# Sheet2.net
KiCad netlist of a schematic drawn in Altium Designer
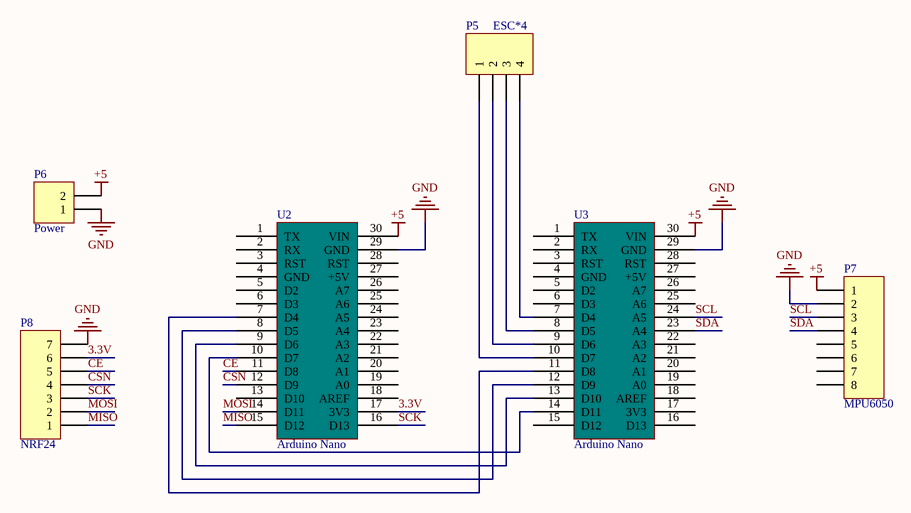
[diagram p0: Sheet2.SchDoc]

(export (version "E")
  (design (tool "Eeschema 10.0.6"))
  (components
    (comp (ref "P5")
      (value "ESC*4")
      (footprint "HDR1X4")
      (description "Header, 4-Pin")
      (fields (field (name "PUBLISHER") "Altium Limited"))
      (libsource (lib "Miscellaneous Connectors") (part "Header 4"))
    )
    (comp (ref "P6")
      (value "Power")
      (footprint "HDR1X2")
      (description "Header, 2-Pin")
      (fields (field (name "PUBLISHER") "Altium Limited"))
      (libsource (lib "Miscellaneous Connectors") (part "Header 2"))
    )
    (comp (ref "P7")
      (value "MPU6050")
      (footprint "HDR1X8")
      (description "Header, 8-Pin")
      (fields (field (name "PUBLISHER") "Altium Limited"))
      (libsource (lib "Miscellaneous Connectors") (part "Header 8"))
    )
    (comp (ref "P8")
      (value "NRF24")
      (footprint "HDR1X7")
      (description "Header, 7-Pin")
      (fields (field (name "PUBLISHER") "Altium Limited"))
      (libsource (lib "Miscellaneous Connectors") (part "Header 7"))
    )
    (comp (ref "U2")
      (value "Arduino Nano")
      (footprint "PCBComponent_1")
      (libsource (lib "Nano") (part "Component_1"))
    )
    (comp (ref "U3")
      (value "Arduino Nano")
      (footprint "PCBComponent_1")
      (libsource (lib "Nano") (part "Component_1"))
    )
  )
  (nets
    (net (code "1") (name "+5") (class "Default")
      (node (ref "P6") (pin "2") (pinfunction "2_2") (pintype "passive"))
      (node (ref "P7") (pin "1") (pinfunction "1_1") (pintype "passive"))
      (node (ref "U2") (pin "30") (pinfunction "VIN_30") (pintype "passive"))
      (node (ref "U3") (pin "30") (pinfunction "VIN_30") (pintype "passive"))
    )
    (net (code "2") (name "/3.3V") (class "Default")
      (node (ref "P8") (pin "6") (pinfunction "6_6") (pintype "passive"))
      (node (ref "U2") (pin "17") (pinfunction "3V3_17") (pintype "passive"))
    )
    (net (code "3") (name "/CE") (class "Default")
      (node (ref "P8") (pin "5") (pinfunction "5_5") (pintype "passive"))
      (node (ref "U2") (pin "11") (pinfunction "D8_11") (pintype "passive"))
    )
    (net (code "4") (name "/CSN") (class "Default")
      (node (ref "P8") (pin "4") (pinfunction "4_4") (pintype "passive"))
      (node (ref "U2") (pin "12") (pinfunction "D9_12") (pintype "passive"))
    )
    (net (code "5") (name "/MISO") (class "Default")
      (node (ref "P8") (pin "1") (pinfunction "1_1") (pintype "passive"))
      (node (ref "U2") (pin "15") (pinfunction "D12_15") (pintype "passive"))
    )
    (net (code "6") (name "/MOSI") (class "Default")
      (node (ref "P8") (pin "2") (pinfunction "2_2") (pintype "passive"))
      (node (ref "U2") (pin "14") (pinfunction "D11_14") (pintype "passive"))
    )
    (net (code "7") (name "/SCK") (class "Default")
      (node (ref "P8") (pin "3") (pinfunction "3_3") (pintype "passive"))
      (node (ref "U2") (pin "16") (pinfunction "D13_16") (pintype "passive"))
    )
    (net (code "8") (name "/SCL") (class "Default")
      (node (ref "P7") (pin "3") (pinfunction "3_3") (pintype "passive"))
      (node (ref "U3") (pin "24") (pinfunction "A5_24") (pintype "passive"))
    )
    (net (code "9") (name "/SDA") (class "Default")
      (node (ref "P7") (pin "4") (pinfunction "4_4") (pintype "passive"))
      (node (ref "U3") (pin "23") (pinfunction "A4_23") (pintype "passive"))
    )
    (net (code "10") (name "GND") (class "Default")
      (node (ref "P6") (pin "1") (pinfunction "1_1") (pintype "passive"))
      (node (ref "P7") (pin "2") (pinfunction "2_2") (pintype "passive"))
      (node (ref "P8") (pin "7") (pinfunction "7_7") (pintype "passive"))
      (node (ref "U2") (pin "29") (pinfunction "GND_29") (pintype "passive"))
      (node (ref "U3") (pin "29") (pinfunction "GND_29") (pintype "passive"))
    )
    (net (code "11") (name "Net-(U2-D4)") (class "Default")
      (node (ref "U2") (pin "7") (pinfunction "D4_7") (pintype "passive"))
      (node (ref "U3") (pin "11") (pinfunction "D8_11") (pintype "passive"))
    )
    (net (code "12") (name "Net-(U2-D5)") (class "Default")
      (node (ref "U2") (pin "8") (pinfunction "D5_8") (pintype "passive"))
      (node (ref "U3") (pin "12") (pinfunction "D9_12") (pintype "passive"))
    )
    (net (code "13") (name "Net-(U2-D6)") (class "Default")
      (node (ref "U2") (pin "9") (pinfunction "D6_9") (pintype "passive"))
      (node (ref "U3") (pin "13") (pinfunction "D10_13") (pintype "passive"))
    )
    (net (code "14") (name "Net-(U2-D7)") (class "Default")
      (node (ref "U2") (pin "10") (pinfunction "D7_10") (pintype "passive"))
      (node (ref "U3") (pin "14") (pinfunction "D11_14") (pintype "passive"))
    )
    (net (code "15") (name "Net-(U3-D4)") (class "Default")
      (node (ref "P5") (pin "4") (pinfunction "4_4") (pintype "passive"))
      (node (ref "U3") (pin "7") (pinfunction "D4_7") (pintype "passive"))
    )
    (net (code "16") (name "Net-(U3-D5)") (class "Default")
      (node (ref "P5") (pin "3") (pinfunction "3_3") (pintype "passive"))
      (node (ref "U3") (pin "8") (pinfunction "D5_8") (pintype "passive"))
    )
    (net (code "17") (name "Net-(U3-D6)") (class "Default")
      (node (ref "P5") (pin "2") (pinfunction "2_2") (pintype "passive"))
      (node (ref "U3") (pin "9") (pinfunction "D6_9") (pintype "passive"))
    )
    (net (code "18") (name "Net-(U3-D7)") (class "Default")
      (node (ref "P5") (pin "1") (pinfunction "1_1") (pintype "passive"))
      (node (ref "U3") (pin "10") (pinfunction "D7_10") (pintype "passive"))
    )
    (net (code "19") (name "unconnected-(P7-Pad5)") (class "Default")
      (node (ref "P7") (pin "5") (pinfunction "5_5") (pintype "passive"))
    )
    (net (code "20") (name "unconnected-(P7-Pad6)") (class "Default")
      (node (ref "P7") (pin "6") (pinfunction "6_6") (pintype "passive"))
    )
    (net (code "21") (name "unconnected-(P7-Pad7)") (class "Default")
      (node (ref "P7") (pin "7") (pinfunction "7_7") (pintype "passive"))
    )
    (net (code "22") (name "unconnected-(P7-Pad8)") (class "Default")
      (node (ref "P7") (pin "8") (pinfunction "8_8") (pintype "passive"))
    )
    (net (code "23") (name "unconnected-(U2-+5V-Pad27)") (class "Default")
      (node (ref "U2") (pin "27") (pinfunction "+5V_27") (pintype "passive"))
    )
    (net (code "24") (name "unconnected-(U2-A0-Pad19)") (class "Default")
      (node (ref "U2") (pin "19") (pinfunction "A0_19") (pintype "passive"))
    )
    (net (code "25") (name "unconnected-(U2-A1-Pad20)") (class "Default")
      (node (ref "U2") (pin "20") (pinfunction "A1_20") (pintype "passive"))
    )
    (net (code "26") (name "unconnected-(U2-A2-Pad21)") (class "Default")
      (node (ref "U2") (pin "21") (pinfunction "A2_21") (pintype "passive"))
    )
    (net (code "27") (name "unconnected-(U2-A3-Pad22)") (class "Default")
      (node (ref "U2") (pin "22") (pinfunction "A3_22") (pintype "passive"))
    )
    (net (code "28") (name "unconnected-(U2-A4-Pad23)") (class "Default")
      (node (ref "U2") (pin "23") (pinfunction "A4_23") (pintype "passive"))
    )
    (net (code "29") (name "unconnected-(U2-A5-Pad24)") (class "Default")
      (node (ref "U2") (pin "24") (pinfunction "A5_24") (pintype "passive"))
    )
    (net (code "30") (name "unconnected-(U2-A6-Pad25)") (class "Default")
      (node (ref "U2") (pin "25") (pinfunction "A6_25") (pintype "passive"))
    )
    (net (code "31") (name "unconnected-(U2-A7-Pad26)") (class "Default")
      (node (ref "U2") (pin "26") (pinfunction "A7_26") (pintype "passive"))
    )
    (net (code "32") (name "unconnected-(U2-AREF-Pad18)") (class "Default")
      (node (ref "U2") (pin "18") (pinfunction "AREF_18") (pintype "passive"))
    )
    (net (code "33") (name "unconnected-(U2-D2-Pad5)") (class "Default")
      (node (ref "U2") (pin "5") (pinfunction "D2_5") (pintype "passive"))
    )
    (net (code "34") (name "unconnected-(U2-D3-Pad6)") (class "Default")
      (node (ref "U2") (pin "6") (pinfunction "D3_6") (pintype "passive"))
    )
    (net (code "35") (name "unconnected-(U2-D10-Pad13)") (class "Default")
      (node (ref "U2") (pin "13") (pinfunction "D10_13") (pintype "passive"))
    )
    (net (code "36") (name "unconnected-(U2-GND-Pad4)") (class "Default")
      (node (ref "U2") (pin "4") (pinfunction "GND_4") (pintype "passive"))
    )
    (net (code "37") (name "unconnected-(U2-RST-Pad3)") (class "Default")
      (node (ref "U2") (pin "3") (pinfunction "RST_3") (pintype "passive"))
    )
    (net (code "38") (name "unconnected-(U2-RST-Pad28)") (class "Default")
      (node (ref "U2") (pin "28") (pinfunction "RST_28") (pintype "passive"))
    )
    (net (code "39") (name "unconnected-(U2-RX-Pad2)") (class "Default")
      (node (ref "U2") (pin "2") (pinfunction "RX_2") (pintype "passive"))
    )
    (net (code "40") (name "unconnected-(U2-TX-Pad1)") (class "Default")
      (node (ref "U2") (pin "1") (pinfunction "TX_1") (pintype "passive"))
    )
    (net (code "41") (name "unconnected-(U3-+5V-Pad27)") (class "Default")
      (node (ref "U3") (pin "27") (pinfunction "+5V_27") (pintype "passive"))
    )
    (net (code "42") (name "unconnected-(U3-3V3-Pad17)") (class "Default")
      (node (ref "U3") (pin "17") (pinfunction "3V3_17") (pintype "passive"))
    )
    (net (code "43") (name "unconnected-(U3-A0-Pad19)") (class "Default")
      (node (ref "U3") (pin "19") (pinfunction "A0_19") (pintype "passive"))
    )
    (net (code "44") (name "unconnected-(U3-A1-Pad20)") (class "Default")
      (node (ref "U3") (pin "20") (pinfunction "A1_20") (pintype "passive"))
    )
    (net (code "45") (name "unconnected-(U3-A2-Pad21)") (class "Default")
      (node (ref "U3") (pin "21") (pinfunction "A2_21") (pintype "passive"))
    )
    (net (code "46") (name "unconnected-(U3-A3-Pad22)") (class "Default")
      (node (ref "U3") (pin "22") (pinfunction "A3_22") (pintype "passive"))
    )
    (net (code "47") (name "unconnected-(U3-A6-Pad25)") (class "Default")
      (node (ref "U3") (pin "25") (pinfunction "A6_25") (pintype "passive"))
    )
    (net (code "48") (name "unconnected-(U3-A7-Pad26)") (class "Default")
      (node (ref "U3") (pin "26") (pinfunction "A7_26") (pintype "passive"))
    )
    (net (code "49") (name "unconnected-(U3-AREF-Pad18)") (class "Default")
      (node (ref "U3") (pin "18") (pinfunction "AREF_18") (pintype "passive"))
    )
    (net (code "50") (name "unconnected-(U3-D2-Pad5)") (class "Default")
      (node (ref "U3") (pin "5") (pinfunction "D2_5") (pintype "passive"))
    )
    (net (code "51") (name "unconnected-(U3-D3-Pad6)") (class "Default")
      (node (ref "U3") (pin "6") (pinfunction "D3_6") (pintype "passive"))
    )
    (net (code "52") (name "unconnected-(U3-D12-Pad15)") (class "Default")
      (node (ref "U3") (pin "15") (pinfunction "D12_15") (pintype "passive"))
    )
    (net (code "53") (name "unconnected-(U3-D13-Pad16)") (class "Default")
      (node (ref "U3") (pin "16") (pinfunction "D13_16") (pintype "passive"))
    )
    (net (code "54") (name "unconnected-(U3-GND-Pad4)") (class "Default")
      (node (ref "U3") (pin "4") (pinfunction "GND_4") (pintype "passive"))
    )
    (net (code "55") (name "unconnected-(U3-RST-Pad3)") (class "Default")
      (node (ref "U3") (pin "3") (pinfunction "RST_3") (pintype "passive"))
    )
    (net (code "56") (name "unconnected-(U3-RST-Pad28)") (class "Default")
      (node (ref "U3") (pin "28") (pinfunction "RST_28") (pintype "passive"))
    )
    (net (code "57") (name "unconnected-(U3-RX-Pad2)") (class "Default")
      (node (ref "U3") (pin "2") (pinfunction "RX_2") (pintype "passive"))
    )
    (net (code "58") (name "unconnected-(U3-TX-Pad1)") (class "Default")
      (node (ref "U3") (pin "1") (pinfunction "TX_1") (pintype "passive"))
    )
  )
)
